# power.net
KiCad netlist of a schematic drawn in Altium Designer
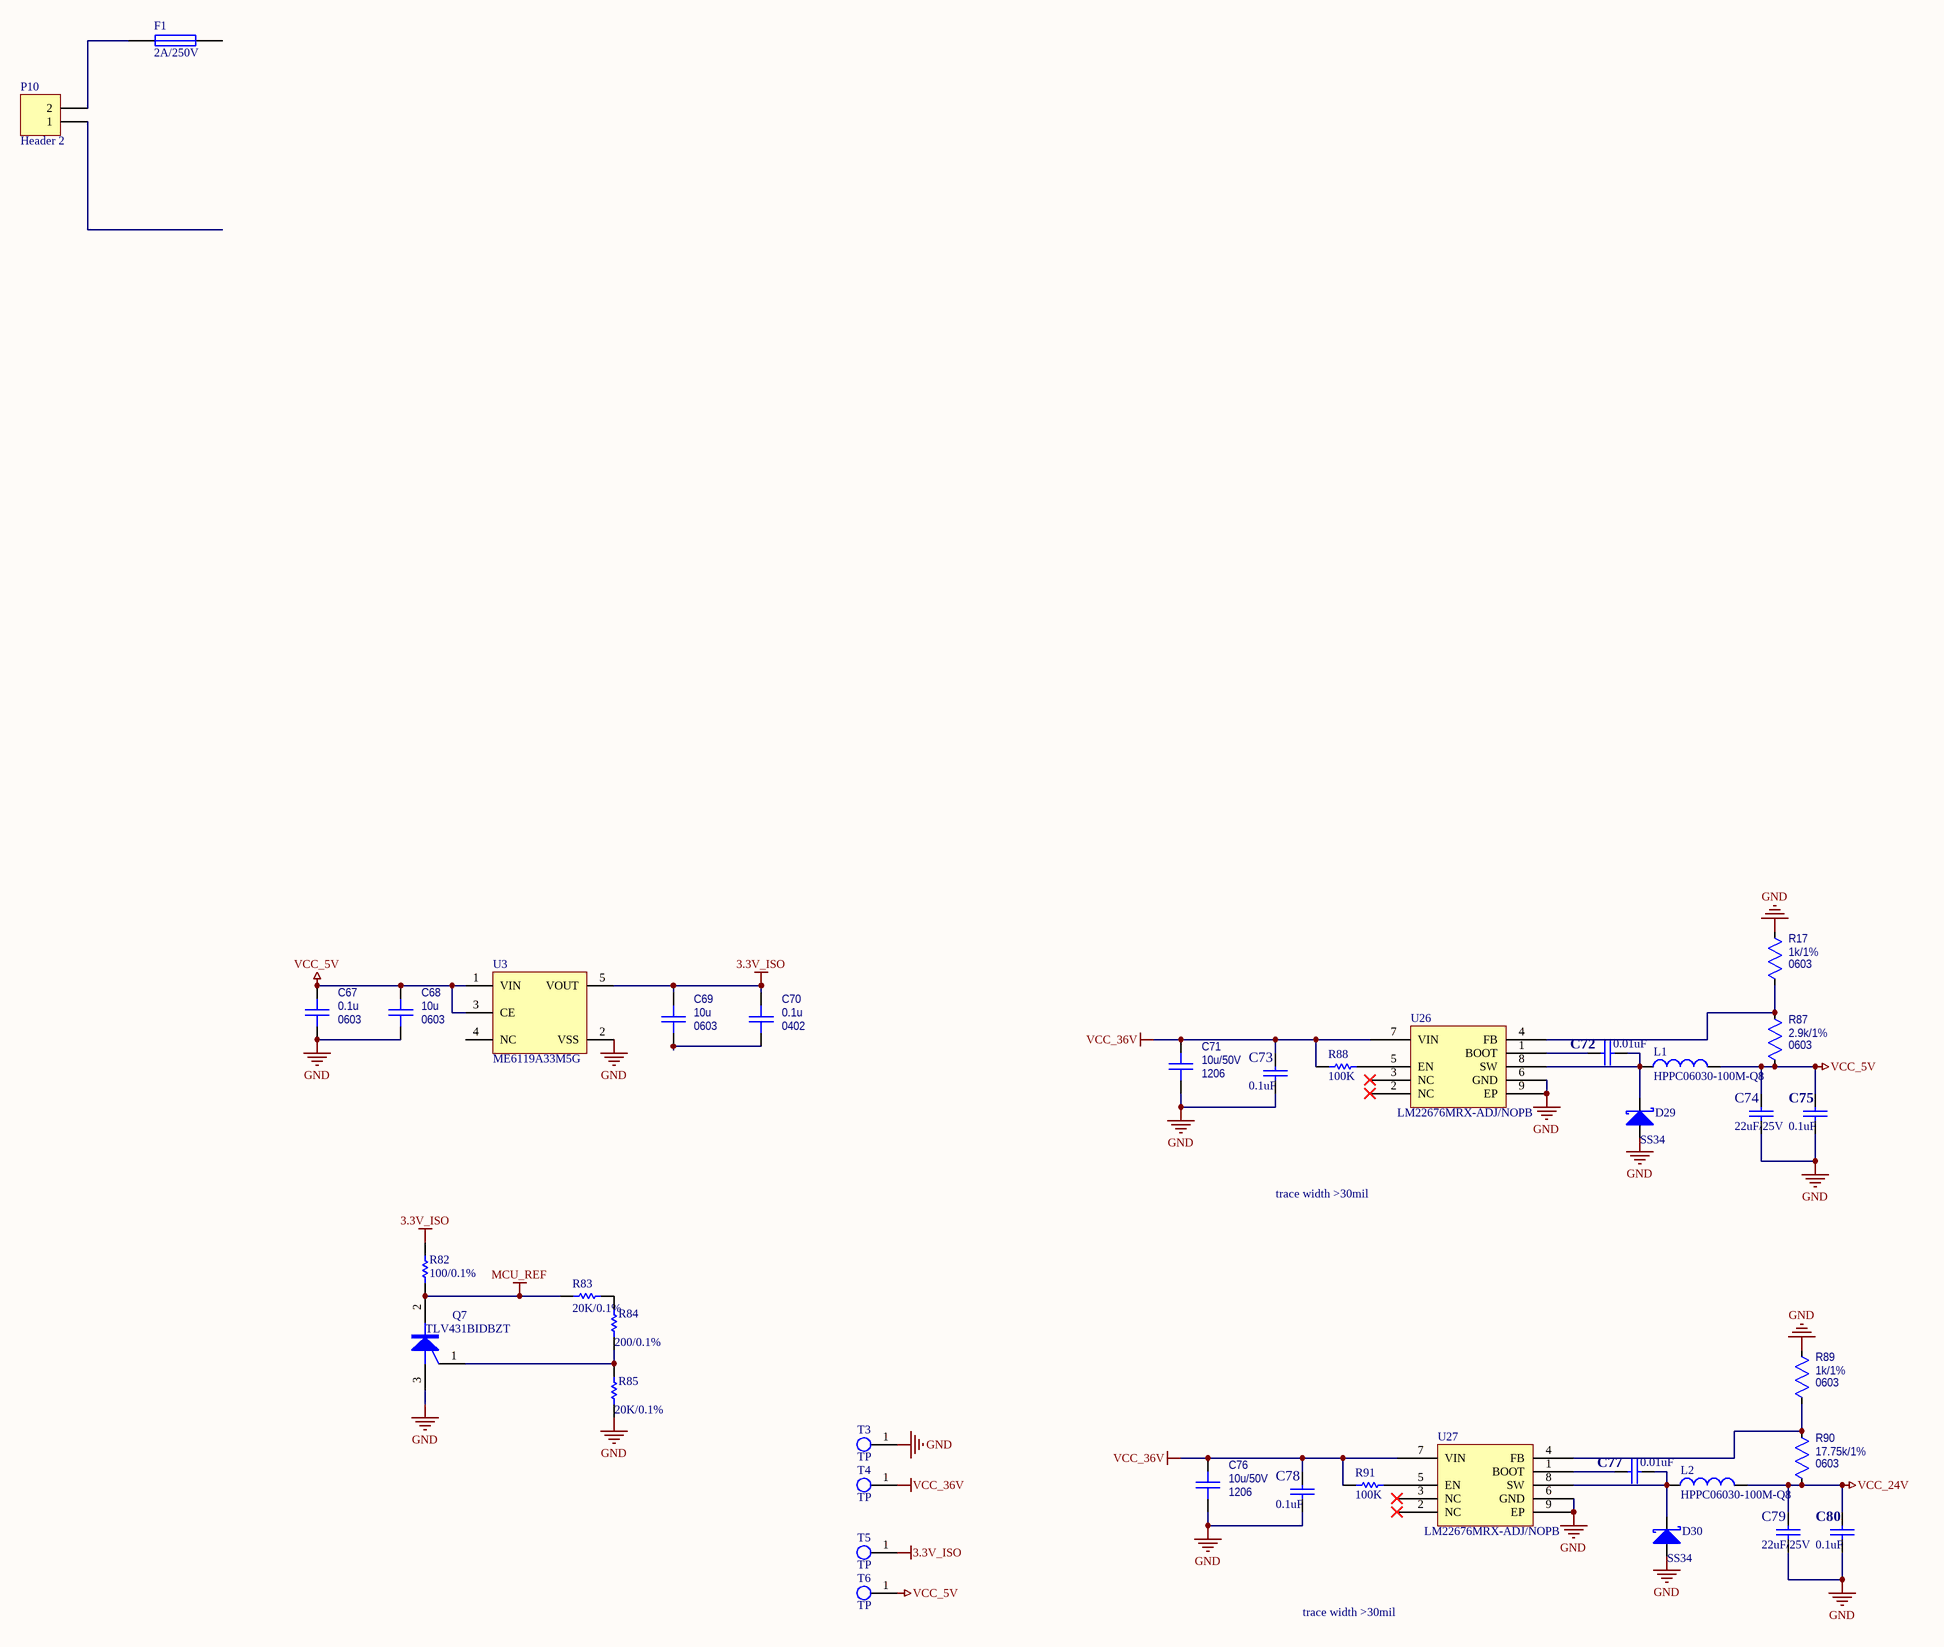
[diagram p0: power.SchDoc]

(export (version "E")
  (design (tool "Eeschema 10.0.6"))
  (components
    (comp (ref "C67")
      (value "0.1u")
      (footprint "CAPC1608X092N_0603")
      (description "Capacitor, MLCC")
      (fields
        (field (name "MANUFACTURER") "KEMET")
        (field (name "PARTNUMBER") "C0603C104M5RACTU")
        (field (name "PACKAGE") "0603")
      )
      (libsource (lib "Karl") (part "Capacitor_0603"))
    )
    (comp (ref "C68")
      (value "10u")
      (footprint "CAPC1608X092N_0603")
      (description "Capacitor, MLCC")
      (fields
        (field (name "MANUFACTURER") "Murata Electronics")
        (field (name "PARTNUMBER") "GRM188R61A106KE69D")
        (field (name "PACKAGE") "0603")
      )
      (libsource (lib "Karl") (part "Capacitor_0603"))
    )
    (comp (ref "C69")
      (value "10u")
      (footprint "CAPC1608X092N_0603")
      (description "Capacitor, MLCC")
      (fields
        (field (name "MANUFACTURER") "Murata Electronics")
        (field (name "PARTNUMBER") "GRM188R61A106KE69D")
        (field (name "PACKAGE") "0603")
      )
      (libsource (lib "Karl") (part "Capacitor_0603"))
    )
    (comp (ref "C70")
      (value "0.1u")
      (footprint "CAPC1005X056N_0402")
      (description "Capacitor, MLCC")
      (fields
        (field (name "MANUFACTURER") "Murata Electronics")
        (field (name "PARTNUMBER") "GRM155R71C104KA88J")
        (field (name "PACKAGE") "0402")
      )
      (libsource (lib "Karl") (part "Capacitor_0402"))
    )
    (comp (ref "C71")
      (value "10u/50V")
      (footprint "1206C")
      (fields
        (field (name "PARTNUMBER") "C1206C106M3PACTU")
        (field (name "TOLERANCE") "[tol]")
        (field (name "PACKAGE") "1206")
        (field (name "Comment") "Capacitor_1206")
      )
      (libsource (lib "Karl") (part "Capacitor_1206"))
    )
    (comp (ref "C72") (value "0.01uF") (footprint "0603C") (libsource (lib "*") (part "CAP")))
    (comp (ref "C73") (value "0.1uF") (footprint "0603C") (libsource (lib "*") (part "CAP")))
    (comp (ref "C74") (value "22uF/25V") (footprint "1206C") (libsource (lib "*") (part "CAP")))
    (comp (ref "C75") (value "0.1uF") (footprint "0603C") (libsource (lib "*") (part "CAP")))
    (comp (ref "C76")
      (value "10u/50V")
      (footprint "1206C")
      (fields
        (field (name "PARTNUMBER") "C1206C106M3PACTU")
        (field (name "TOLERANCE") "[tol]")
        (field (name "PACKAGE") "1206")
        (field (name "Comment") "Capacitor_1206")
      )
      (libsource (lib "Karl") (part "Capacitor_1206"))
    )
    (comp (ref "C77") (value "0.01uF") (footprint "0603C") (libsource (lib "*") (part "CAP")))
    (comp (ref "C78") (value "0.1uF") (footprint "0603C") (libsource (lib "*") (part "CAP")))
    (comp (ref "C79") (value "22uF/25V") (footprint "1206C") (libsource (lib "*") (part "CAP")))
    (comp (ref "C80") (value "0.1uF") (footprint "0603C") (libsource (lib "*") (part "CAP")))
    (comp (ref "D29") (value "SS34") (footprint "SMA") (libsource (lib "*") (part "DIODE S")))
    (comp (ref "D30") (value "SS34") (footprint "SMA") (libsource (lib "*") (part "DIODE S")))
    (comp (ref "F1")
      (value "2A/250V")
      (footprint "可视开关电源保险丝座")
      (description "Fuse")
      (fields (field (name "PUBLISHER") "Altium Limited"))
      (libsource (lib "Miscellaneous Devices") (part "Fuse 1"))
    )
    (comp (ref "L1")
      (value "HPPC06030-100M-Q8")
      (footprint "IND-SMD-L7.3-W6")
      (fields (field (name "PARTNUMBER") "1276AS-H-100M=P2"))
      (libsource (lib "Bogen") (part "1276AS-H-100M=P2"))
    )
    (comp (ref "L2")
      (value "HPPC06030-100M-Q8")
      (footprint "IND-SMD-L7.3-W6")
      (fields (field (name "PARTNUMBER") "1276AS-H-100M=P2"))
      (libsource (lib "Bogen") (part "1276AS-H-100M=P2"))
    )
    (comp (ref "P10")
      (value "Header 2")
      (footprint "HDR1X2")
      (description "Header, 2-Pin")
      (fields (field (name "PUBLISHER") "Altium Limited"))
      (libsource (lib "Miscellaneous Connectors") (part "Header 2"))
    )
    (comp (ref "Q7")
      (value "TLV431BIDBZT")
      (footprint "SOT23-3")
      (description "Programmable Unijunction Transistor")
      (fields (field (name "PUBLISHER") "Altium Limited"))
      (libsource (lib "Miscellaneous Devices") (part "PUT"))
    )
    (comp (ref "R17")
      (value "1k/1%")
      (footprint "0603R")
      (fields
        (field (name "PARTNUMBER") "RC0603FR-1075KL")
        (field (name "TOLERANCE") "tol")
        (field (name "PACKAGE") "0603")
        (field (name "Comment") "Resistor_0603")
      )
      (libsource (lib "Karl") (part "Resistor_0603"))
    )
    (comp (ref "R82")
      (value "100/0.1%")
      (footprint "0603R")
      (description "Resistor")
      (fields (field (name "PUBLISHER") "Altium Limited"))
      (libsource (lib "Miscellaneous Devices") (part "Res1"))
    )
    (comp (ref "R83")
      (value "20K/0.1%")
      (footprint "0603R")
      (description "Resistor")
      (fields (field (name "Comment") "1K/0.1%") (field (name "PUBLISHER") "Altium Limited"))
      (libsource (lib "Miscellaneous Devices") (part "Res1"))
    )
    (comp (ref "R84")
      (value "200/0.1%")
      (footprint "0603R")
      (description "Resistor")
      (fields (field (name "Comment") "1K/0.1%") (field (name "PUBLISHER") "Altium Limited"))
      (libsource (lib "Miscellaneous Devices") (part "Res1"))
    )
    (comp (ref "R85")
      (value "20K/0.1%")
      (footprint "0603R")
      (description "Resistor")
      (fields (field (name "Comment") "1K/0.1%") (field (name "PUBLISHER") "Altium Limited"))
      (libsource (lib "Miscellaneous Devices") (part "Res1"))
    )
    (comp (ref "R87")
      (value "2.9k/1%")
      (footprint "0603R")
      (fields
        (field (name "PARTNUMBER") "RC0603FR-1075KL")
        (field (name "TOLERANCE") "tol")
        (field (name "PACKAGE") "0603")
        (field (name "Comment") "Resistor_0603")
      )
      (libsource (lib "Karl") (part "Resistor_0603"))
    )
    (comp (ref "R88")
      (value "100K")
      (footprint "0603R")
      (fields (field (name "PUBLISHER") "Altium Limited"))
      (libsource (lib "Miscellaneous Devices") (part "Res1"))
    )
    (comp (ref "R89")
      (value "1k/1%")
      (footprint "0603R")
      (fields
        (field (name "PARTNUMBER") "RC0603FR-1075KL")
        (field (name "TOLERANCE") "tol")
        (field (name "PACKAGE") "0603")
        (field (name "Comment") "Resistor_0603")
      )
      (libsource (lib "Karl") (part "Resistor_0603"))
    )
    (comp (ref "R90")
      (value "17.75k/1%")
      (footprint "0603R")
      (fields
        (field (name "PARTNUMBER") "RC0603FR-1075KL")
        (field (name "TOLERANCE") "tol")
        (field (name "PACKAGE") "0603")
        (field (name "Comment") "Resistor_0603")
      )
      (libsource (lib "Karl") (part "Resistor_0603"))
    )
    (comp (ref "R91")
      (value "100K")
      (footprint "0603R")
      (fields (field (name "PUBLISHER") "Altium Limited"))
      (libsource (lib "Miscellaneous Devices") (part "Res1"))
    )
    (comp (ref "T3") (value "TP") (footprint "TPD") (libsource (lib "Schlib_20110825") (part "TP")))
    (comp (ref "T4") (value "TP") (footprint "TPD") (libsource (lib "Schlib_20110825") (part "TP")))
    (comp (ref "T5") (value "TP") (footprint "TPD") (libsource (lib "Schlib_20110825") (part "TP")))
    (comp (ref "T6") (value "TP") (footprint "TPD") (libsource (lib "Schlib_20110825") (part "TP")))
    (comp (ref "U3")
      (value "ME6119A33M5G")
      (footprint "MCRN-SOT23-5_V")
      (libsource (lib "Bogen") (part "ME6119C50M5G"))
    )
    (comp (ref "U26")
      (value "LM22676MRX-ADJ/NOPB")
      (footprint "SOP127P600X168_HS-8N")
      (libsource (lib "Schlib1") (part "LM22676MR-5.0"))
    )
    (comp (ref "U27")
      (value "LM22676MRX-ADJ/NOPB")
      (footprint "SOP127P600X168_HS-8N")
      (libsource (lib "Schlib1") (part "LM22676MR-5.0"))
    )
  )
  (nets
    (net (code "1") (name "3.3V_ISO") (class "Default")
      (node (ref "C69") (pin "1") (pinfunction "1_1") (pintype "passive"))
      (node (ref "C70") (pin "1") (pinfunction "1_1") (pintype "passive"))
      (node (ref "R82") (pin "1") (pinfunction "1_1") (pintype "passive"))
      (node (ref "T5") (pin "1") (pintype "passive"))
      (node (ref "U3") (pin "5") (pinfunction "VOUT_5") (pintype "passive"))
    )
    (net (code "2") (name "GND") (class "Default")
      (node (ref "C67") (pin "2") (pinfunction "2_2") (pintype "passive"))
      (node (ref "C68") (pin "2") (pinfunction "2_2") (pintype "passive"))
      (node (ref "C71") (pin "2") (pinfunction "2_2") (pintype "passive"))
      (node (ref "C73") (pin "1") (pinfunction "1_1") (pintype "passive"))
      (node (ref "C74") (pin "1") (pinfunction "1_1") (pintype "passive"))
      (node (ref "C75") (pin "2") (pinfunction "2_2") (pintype "passive"))
      (node (ref "C76") (pin "2") (pinfunction "2_2") (pintype "passive"))
      (node (ref "C78") (pin "1") (pinfunction "1_1") (pintype "passive"))
      (node (ref "C79") (pin "1") (pinfunction "1_1") (pintype "passive"))
      (node (ref "C80") (pin "2") (pinfunction "2_2") (pintype "passive"))
      (node (ref "D29") (pin "1") (pinfunction "A_1") (pintype "passive"))
      (node (ref "D30") (pin "1") (pinfunction "A_1") (pintype "passive"))
      (node (ref "Q7") (pin "3") (pinfunction "A_3") (pintype "passive"))
      (node (ref "R17") (pin "2") (pinfunction "2_2") (pintype "passive"))
      (node (ref "R85") (pin "2") (pinfunction "2_2") (pintype "passive"))
      (node (ref "R89") (pin "2") (pinfunction "2_2") (pintype "passive"))
      (node (ref "T3") (pin "1") (pintype "passive"))
      (node (ref "U26") (pin "6") (pinfunction "GND_6") (pintype "passive"))
      (node (ref "U26") (pin "9") (pinfunction "EP_9") (pintype "passive"))
      (node (ref "U27") (pin "6") (pinfunction "GND_6") (pintype "passive"))
      (node (ref "U27") (pin "9") (pinfunction "EP_9") (pintype "passive"))
      (node (ref "U3") (pin "2") (pinfunction "VSS_2") (pintype "passive"))
    )
    (net (code "3") (name "MCU_REF") (class "Default")
      (node (ref "Q7") (pin "2") (pinfunction "K_2") (pintype "passive"))
      (node (ref "R82") (pin "2") (pinfunction "2_2") (pintype "passive"))
      (node (ref "R83") (pin "1") (pinfunction "1_1") (pintype "passive"))
    )
    (net (code "4") (name "Net-(C69-Pad2)") (class "Default")
      (node (ref "C69") (pin "2") (pinfunction "2_2") (pintype "passive"))
      (node (ref "C70") (pin "2") (pinfunction "2_2") (pintype "passive"))
    )
    (net (code "5") (name "Net-(D29-K)") (class "Default")
      (node (ref "C72") (pin "1") (pinfunction "1_1") (pintype "passive"))
      (node (ref "D29") (pin "2") (pinfunction "K_2") (pintype "passive"))
      (node (ref "L1") (pin "1") (pinfunction "1_1") (pintype "passive"))
      (node (ref "U26") (pin "8") (pinfunction "SW_8") (pintype "passive"))
    )
    (net (code "6") (name "Net-(D30-K)") (class "Default")
      (node (ref "C77") (pin "1") (pinfunction "1_1") (pintype "passive"))
      (node (ref "D30") (pin "2") (pinfunction "K_2") (pintype "passive"))
      (node (ref "L2") (pin "1") (pinfunction "1_1") (pintype "passive"))
      (node (ref "U27") (pin "8") (pinfunction "SW_8") (pintype "passive"))
    )
    (net (code "7") (name "Net-(F1-Pad1)") (class "Default")
      (node (ref "F1") (pin "1") (pinfunction "1_1") (pintype "passive"))
      (node (ref "P10") (pin "2") (pinfunction "2_2") (pintype "passive"))
    )
    (net (code "8") (name "Net-(Q7-G)") (class "Default")
      (node (ref "Q7") (pin "1") (pinfunction "G_1") (pintype "passive"))
      (node (ref "R84") (pin "2") (pinfunction "2_2") (pintype "passive"))
      (node (ref "R85") (pin "1") (pinfunction "1_1") (pintype "passive"))
    )
    (net (code "9") (name "Net-(R83-Pad2)") (class "Default")
      (node (ref "R83") (pin "2") (pinfunction "2_2") (pintype "passive"))
      (node (ref "R84") (pin "1") (pinfunction "1_1") (pintype "passive"))
    )
    (net (code "10") (name "Net-(U26-BOOT)") (class "Default")
      (node (ref "C72") (pin "2") (pinfunction "2_2") (pintype "passive"))
      (node (ref "U26") (pin "1") (pinfunction "BOOT_1") (pintype "passive"))
    )
    (net (code "11") (name "Net-(U26-EN)") (class "Default")
      (node (ref "R88") (pin "1") (pinfunction "1_1") (pintype "passive"))
      (node (ref "U26") (pin "5") (pinfunction "EN_5") (pintype "passive"))
    )
    (net (code "12") (name "Net-(U26-FB)") (class "Default")
      (node (ref "R17") (pin "1") (pinfunction "1_1") (pintype "passive"))
      (node (ref "R87") (pin "2") (pinfunction "2_2") (pintype "passive"))
      (node (ref "U26") (pin "4") (pinfunction "FB_4") (pintype "passive"))
    )
    (net (code "13") (name "Net-(U27-BOOT)") (class "Default")
      (node (ref "C77") (pin "2") (pinfunction "2_2") (pintype "passive"))
      (node (ref "U27") (pin "1") (pinfunction "BOOT_1") (pintype "passive"))
    )
    (net (code "14") (name "Net-(U27-EN)") (class "Default")
      (node (ref "R91") (pin "1") (pinfunction "1_1") (pintype "passive"))
      (node (ref "U27") (pin "5") (pinfunction "EN_5") (pintype "passive"))
    )
    (net (code "15") (name "Net-(U27-FB)") (class "Default")
      (node (ref "R89") (pin "1") (pinfunction "1_1") (pintype "passive"))
      (node (ref "R90") (pin "2") (pinfunction "2_2") (pintype "passive"))
      (node (ref "U27") (pin "4") (pinfunction "FB_4") (pintype "passive"))
    )
    (net (code "16") (name "VCC_5V") (class "Default")
      (node (ref "C67") (pin "1") (pinfunction "1_1") (pintype "passive"))
      (node (ref "C68") (pin "1") (pinfunction "1_1") (pintype "passive"))
      (node (ref "C74") (pin "2") (pinfunction "2_2") (pintype "passive"))
      (node (ref "C75") (pin "1") (pinfunction "1_1") (pintype "passive"))
      (node (ref "L1") (pin "2") (pinfunction "2_2") (pintype "passive"))
      (node (ref "R87") (pin "1") (pinfunction "1_1") (pintype "passive"))
      (node (ref "T6") (pin "1") (pintype "passive"))
      (node (ref "U3") (pin "1") (pinfunction "VIN_1") (pintype "passive"))
      (node (ref "U3") (pin "3") (pinfunction "CE_3") (pintype "passive"))
    )
    (net (code "17") (name "VCC_24V") (class "Default")
      (node (ref "C79") (pin "2") (pinfunction "2_2") (pintype "passive"))
      (node (ref "C80") (pin "1") (pinfunction "1_1") (pintype "passive"))
      (node (ref "L2") (pin "2") (pinfunction "2_2") (pintype "passive"))
      (node (ref "R90") (pin "1") (pinfunction "1_1") (pintype "passive"))
    )
    (net (code "18") (name "VCC_36V") (class "Default")
      (node (ref "C71") (pin "1") (pinfunction "1_1") (pintype "passive"))
      (node (ref "C73") (pin "2") (pinfunction "2_2") (pintype "passive"))
      (node (ref "C76") (pin "1") (pinfunction "1_1") (pintype "passive"))
      (node (ref "C78") (pin "2") (pinfunction "2_2") (pintype "passive"))
      (node (ref "R88") (pin "2") (pinfunction "2_2") (pintype "passive"))
      (node (ref "R91") (pin "2") (pinfunction "2_2") (pintype "passive"))
      (node (ref "T4") (pin "1") (pintype "passive"))
      (node (ref "U26") (pin "7") (pinfunction "VIN_7") (pintype "passive"))
      (node (ref "U27") (pin "7") (pinfunction "VIN_7") (pintype "passive"))
    )
    (net (code "19") (name "unconnected-(F1-Pad2)") (class "Default")
      (node (ref "F1") (pin "2") (pinfunction "2_2") (pintype "passive"))
    )
    (net (code "20") (name "unconnected-(P10-Pad1)") (class "Default")
      (node (ref "P10") (pin "1") (pinfunction "1_1") (pintype "passive"))
    )
    (net (code "21") (name "unconnected-(U3-NC-Pad4)") (class "Default")
      (node (ref "U3") (pin "4") (pinfunction "NC_4") (pintype "passive"))
    )
    (net (code "22") (name "unconnected-(U26-NC-Pad2)") (class "Default")
      (node (ref "U26") (pin "2") (pinfunction "NC_2") (pintype "passive+no_connect"))
    )
    (net (code "23") (name "unconnected-(U26-NC-Pad3)") (class "Default")
      (node (ref "U26") (pin "3") (pinfunction "NC_3") (pintype "passive+no_connect"))
    )
    (net (code "24") (name "unconnected-(U27-NC-Pad2)") (class "Default")
      (node (ref "U27") (pin "2") (pinfunction "NC_2") (pintype "passive+no_connect"))
    )
    (net (code "25") (name "unconnected-(U27-NC-Pad3)") (class "Default")
      (node (ref "U27") (pin "3") (pinfunction "NC_3") (pintype "passive+no_connect"))
    )
  )
)
